# VIA_PAR_Adapter_1541C.net
KiCad netlist of a schematic drawn in EAGLE
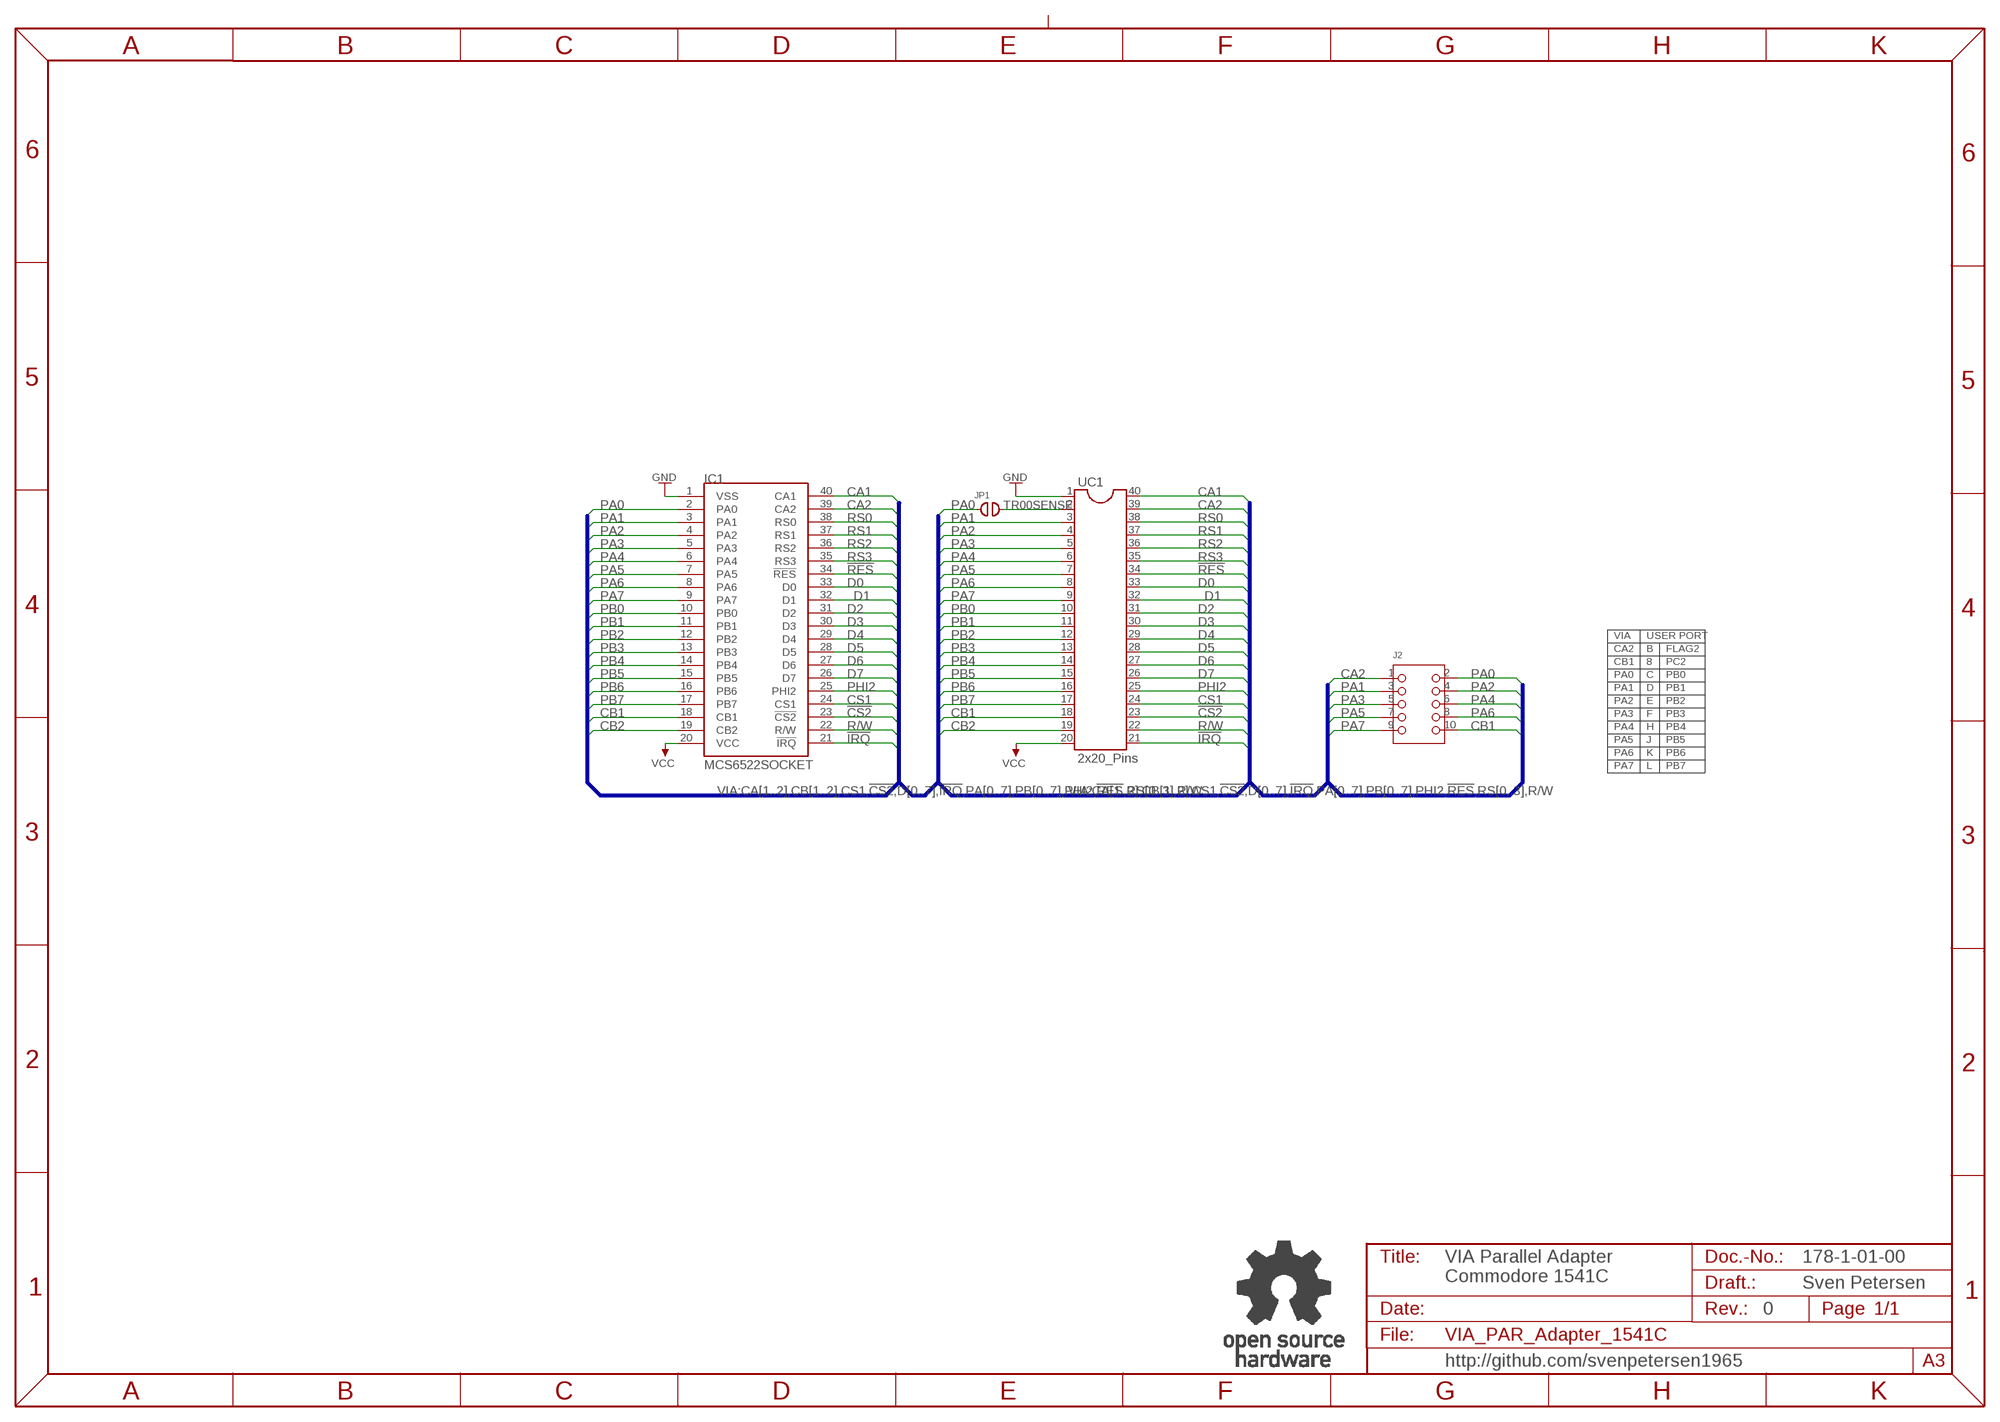
[diagram p0: schematic, sheet 1]

(export (version "E")
  (design (tool "Eeschema 10.0.6"))
  (components
    (comp (ref "IC1")
      (value "MCS6522SOCKET")
      (footprint "eagle-import:GS40P")
      (libsource (lib "eagle-import") (part "MCS6522SOCKET"))
    )
    (comp (ref "J2")
      (value "2X05WV")
      (footprint "eagle-import:2X05WV")
      (libsource (lib "eagle-import") (part "2X05WV"))
    )
    (comp (ref "JP1")
      (value "COMBI_2P")
      (footprint "eagle-import:COMBI-2P")
      (libsource (lib "eagle-import") (part "COMBI_2P"))
    )
    (comp (ref "U$10")
      (value "OPEN_SOURCE_HW")
      (footprint "eagle-import:OPENHW")
      (libsource (lib "eagle-import") (part "OPEN_SOURCE_HW"))
    )
    (comp (ref "UC1")
      (value "2x20_Pins")
      (footprint "eagle-import:DIL40_PINS_SS")
      (libsource (lib "eagle-import") (part "IC_DIL40"))
    )
  )
  (nets
    (net (code "1") (name "/CA1") (class "Default")
      (node (ref "IC1") (pin "40") (pinfunction "CA1_40") (pintype "bidirectional"))
      (node (ref "UC1") (pin "40") (pinfunction "40_40") (pintype "passive"))
    )
    (net (code "2") (name "/CA2") (class "Default")
      (node (ref "IC1") (pin "39") (pinfunction "CA2_39") (pintype "input"))
      (node (ref "J2") (pin "1") (pinfunction "1_1") (pintype "passive"))
      (node (ref "UC1") (pin "39") (pinfunction "39_39") (pintype "passive"))
    )
    (net (code "3") (name "/CB1") (class "Default")
      (node (ref "IC1") (pin "18") (pinfunction "CB1_18") (pintype "bidirectional"))
      (node (ref "J2") (pin "10") (pinfunction "10_10") (pintype "passive"))
      (node (ref "UC1") (pin "18") (pinfunction "18_18") (pintype "passive"))
    )
    (net (code "4") (name "/CB2") (class "Default")
      (node (ref "IC1") (pin "19") (pinfunction "CB2_19") (pintype "bidirectional"))
      (node (ref "UC1") (pin "19") (pinfunction "19_19") (pintype "passive"))
    )
    (net (code "5") (name "/CS1") (class "Default")
      (node (ref "IC1") (pin "24") (pinfunction "CS1_24") (pintype "input"))
      (node (ref "UC1") (pin "24") (pinfunction "24_24") (pintype "passive"))
    )
    (net (code "6") (name "/D0") (class "Default")
      (node (ref "IC1") (pin "33") (pinfunction "D0_33") (pintype "bidirectional"))
      (node (ref "UC1") (pin "33") (pinfunction "33_33") (pintype "passive"))
    )
    (net (code "7") (name "/D1") (class "Default")
      (node (ref "IC1") (pin "32") (pinfunction "D1_32") (pintype "bidirectional"))
      (node (ref "UC1") (pin "32") (pinfunction "32_32") (pintype "passive"))
    )
    (net (code "8") (name "/D2") (class "Default")
      (node (ref "IC1") (pin "31") (pinfunction "D2_31") (pintype "bidirectional"))
      (node (ref "UC1") (pin "31") (pinfunction "31_31") (pintype "passive"))
    )
    (net (code "9") (name "/D3") (class "Default")
      (node (ref "IC1") (pin "30") (pinfunction "D3_30") (pintype "bidirectional"))
      (node (ref "UC1") (pin "30") (pinfunction "30_30") (pintype "passive"))
    )
    (net (code "10") (name "/D4") (class "Default")
      (node (ref "IC1") (pin "29") (pinfunction "D4_29") (pintype "bidirectional"))
      (node (ref "UC1") (pin "29") (pinfunction "29_29") (pintype "passive"))
    )
    (net (code "11") (name "/D5") (class "Default")
      (node (ref "IC1") (pin "28") (pinfunction "D5_28") (pintype "bidirectional"))
      (node (ref "UC1") (pin "28") (pinfunction "28_28") (pintype "passive"))
    )
    (net (code "12") (name "/D6") (class "Default")
      (node (ref "IC1") (pin "27") (pinfunction "D6_27") (pintype "bidirectional"))
      (node (ref "UC1") (pin "27") (pinfunction "27_27") (pintype "passive"))
    )
    (net (code "13") (name "/D7") (class "Default")
      (node (ref "IC1") (pin "26") (pinfunction "D7_26") (pintype "bidirectional"))
      (node (ref "UC1") (pin "26") (pinfunction "26_26") (pintype "passive"))
    )
    (net (code "14") (name "/PA0") (class "Default")
      (node (ref "IC1") (pin "2") (pinfunction "PA0_2") (pintype "bidirectional"))
      (node (ref "J2") (pin "2") (pinfunction "2_2") (pintype "passive"))
      (node (ref "JP1") (pin "1") (pinfunction "1_1") (pintype "passive"))
    )
    (net (code "15") (name "/PA1") (class "Default")
      (node (ref "IC1") (pin "3") (pinfunction "PA1_3") (pintype "bidirectional"))
      (node (ref "J2") (pin "3") (pinfunction "3_3") (pintype "passive"))
      (node (ref "UC1") (pin "3") (pinfunction "3_3") (pintype "passive"))
    )
    (net (code "16") (name "/PA2") (class "Default")
      (node (ref "IC1") (pin "4") (pinfunction "PA2_4") (pintype "bidirectional"))
      (node (ref "J2") (pin "4") (pinfunction "4_4") (pintype "passive"))
      (node (ref "UC1") (pin "4") (pinfunction "4_4") (pintype "passive"))
    )
    (net (code "17") (name "/PA3") (class "Default")
      (node (ref "IC1") (pin "5") (pinfunction "PA3_5") (pintype "bidirectional"))
      (node (ref "J2") (pin "5") (pinfunction "5_5") (pintype "passive"))
      (node (ref "UC1") (pin "5") (pinfunction "5_5") (pintype "passive"))
    )
    (net (code "18") (name "/PA4") (class "Default")
      (node (ref "IC1") (pin "6") (pinfunction "PA4_6") (pintype "bidirectional"))
      (node (ref "J2") (pin "6") (pinfunction "6_6") (pintype "passive"))
      (node (ref "UC1") (pin "6") (pinfunction "6_6") (pintype "passive"))
    )
    (net (code "19") (name "/PA5") (class "Default")
      (node (ref "IC1") (pin "7") (pinfunction "PA5_7") (pintype "bidirectional"))
      (node (ref "J2") (pin "7") (pinfunction "7_7") (pintype "passive"))
      (node (ref "UC1") (pin "7") (pinfunction "7_7") (pintype "passive"))
    )
    (net (code "20") (name "/PA6") (class "Default")
      (node (ref "IC1") (pin "8") (pinfunction "PA6_8") (pintype "bidirectional"))
      (node (ref "J2") (pin "8") (pinfunction "8_8") (pintype "passive"))
      (node (ref "UC1") (pin "8") (pinfunction "8_8") (pintype "passive"))
    )
    (net (code "21") (name "/PA7") (class "Default")
      (node (ref "IC1") (pin "9") (pinfunction "PA7_9") (pintype "bidirectional"))
      (node (ref "J2") (pin "9") (pinfunction "9_9") (pintype "passive"))
      (node (ref "UC1") (pin "9") (pinfunction "9_9") (pintype "passive"))
    )
    (net (code "22") (name "/PB0") (class "Default")
      (node (ref "IC1") (pin "10") (pinfunction "PB0_10") (pintype "bidirectional"))
      (node (ref "UC1") (pin "10") (pinfunction "10_10") (pintype "passive"))
    )
    (net (code "23") (name "/PB1") (class "Default")
      (node (ref "IC1") (pin "11") (pinfunction "PB1_11") (pintype "bidirectional"))
      (node (ref "UC1") (pin "11") (pinfunction "11_11") (pintype "passive"))
    )
    (net (code "24") (name "/PB2") (class "Default")
      (node (ref "IC1") (pin "12") (pinfunction "PB2_12") (pintype "bidirectional"))
      (node (ref "UC1") (pin "12") (pinfunction "12_12") (pintype "passive"))
    )
    (net (code "25") (name "/PB3") (class "Default")
      (node (ref "IC1") (pin "13") (pinfunction "PB3_13") (pintype "bidirectional"))
      (node (ref "UC1") (pin "13") (pinfunction "13_13") (pintype "passive"))
    )
    (net (code "26") (name "/PB4") (class "Default")
      (node (ref "IC1") (pin "14") (pinfunction "PB4_14") (pintype "bidirectional"))
      (node (ref "UC1") (pin "14") (pinfunction "14_14") (pintype "passive"))
    )
    (net (code "27") (name "/PB5") (class "Default")
      (node (ref "IC1") (pin "15") (pinfunction "PB5_15") (pintype "bidirectional"))
      (node (ref "UC1") (pin "15") (pinfunction "15_15") (pintype "passive"))
    )
    (net (code "28") (name "/PB6") (class "Default")
      (node (ref "IC1") (pin "16") (pinfunction "PB6_16") (pintype "bidirectional"))
      (node (ref "UC1") (pin "16") (pinfunction "16_16") (pintype "passive"))
    )
    (net (code "29") (name "/PB7") (class "Default")
      (node (ref "IC1") (pin "17") (pinfunction "PB7_17") (pintype "bidirectional"))
      (node (ref "UC1") (pin "17") (pinfunction "17_17") (pintype "passive"))
    )
    (net (code "30") (name "/PHI2") (class "Default")
      (node (ref "IC1") (pin "25") (pinfunction "PHI2_25") (pintype "input"))
      (node (ref "UC1") (pin "25") (pinfunction "25_25") (pintype "passive"))
    )
    (net (code "31") (name "/RS0") (class "Default")
      (node (ref "IC1") (pin "38") (pinfunction "RS0_38") (pintype "input"))
      (node (ref "UC1") (pin "38") (pinfunction "38_38") (pintype "passive"))
    )
    (net (code "32") (name "/RS1") (class "Default")
      (node (ref "IC1") (pin "37") (pinfunction "RS1_37") (pintype "input"))
      (node (ref "UC1") (pin "37") (pinfunction "37_37") (pintype "passive"))
    )
    (net (code "33") (name "/RS2") (class "Default")
      (node (ref "IC1") (pin "36") (pinfunction "RS2_36") (pintype "input"))
      (node (ref "UC1") (pin "36") (pinfunction "36_36") (pintype "passive"))
    )
    (net (code "34") (name "/RS3") (class "Default")
      (node (ref "IC1") (pin "35") (pinfunction "RS3_35") (pintype "input"))
      (node (ref "UC1") (pin "35") (pinfunction "35_35") (pintype "passive"))
    )
    (net (code "35") (name "/R{slash}W") (class "Default")
      (node (ref "IC1") (pin "22") (pinfunction "R/W_22") (pintype "input"))
      (node (ref "UC1") (pin "22") (pinfunction "22_22") (pintype "passive"))
    )
    (net (code "36") (name "/TR00SENSE") (class "Default")
      (node (ref "JP1") (pin "2") (pinfunction "2_2") (pintype "passive"))
      (node (ref "UC1") (pin "2") (pinfunction "2_2") (pintype "passive"))
    )
    (net (code "38") (name "/~{CS2}") (class "Default")
      (node (ref "IC1") (pin "23") (pinfunction "~{CS2}_23") (pintype "input"))
      (node (ref "UC1") (pin "23") (pinfunction "23_23") (pintype "passive"))
    )
    (net (code "39") (name "/~{IRQ}") (class "Default")
      (node (ref "IC1") (pin "21") (pinfunction "~{IRQ}_21") (pintype "output"))
      (node (ref "UC1") (pin "21") (pinfunction "21_21") (pintype "passive"))
    )
    (net (code "40") (name "/~{RES}") (class "Default")
      (node (ref "IC1") (pin "34") (pinfunction "~{RES}_34") (pintype "input"))
      (node (ref "UC1") (pin "34") (pinfunction "34_34") (pintype "passive"))
    )
    (net (code "41") (name "GND") (class "Default")
      (node (ref "IC1") (pin "1") (pinfunction "VSS_1") (pintype "power_in"))
      (node (ref "UC1") (pin "1") (pinfunction "1_1") (pintype "passive"))
    )
    (net (code "42") (name "VCC") (class "Default")
      (node (ref "IC1") (pin "20") (pinfunction "VCC_20") (pintype "power_in"))
      (node (ref "UC1") (pin "20") (pinfunction "20_20") (pintype "passive"))
    )
  )
)
